# DSDLink.net
KiCad netlist of a schematic drawn in Altium Designer
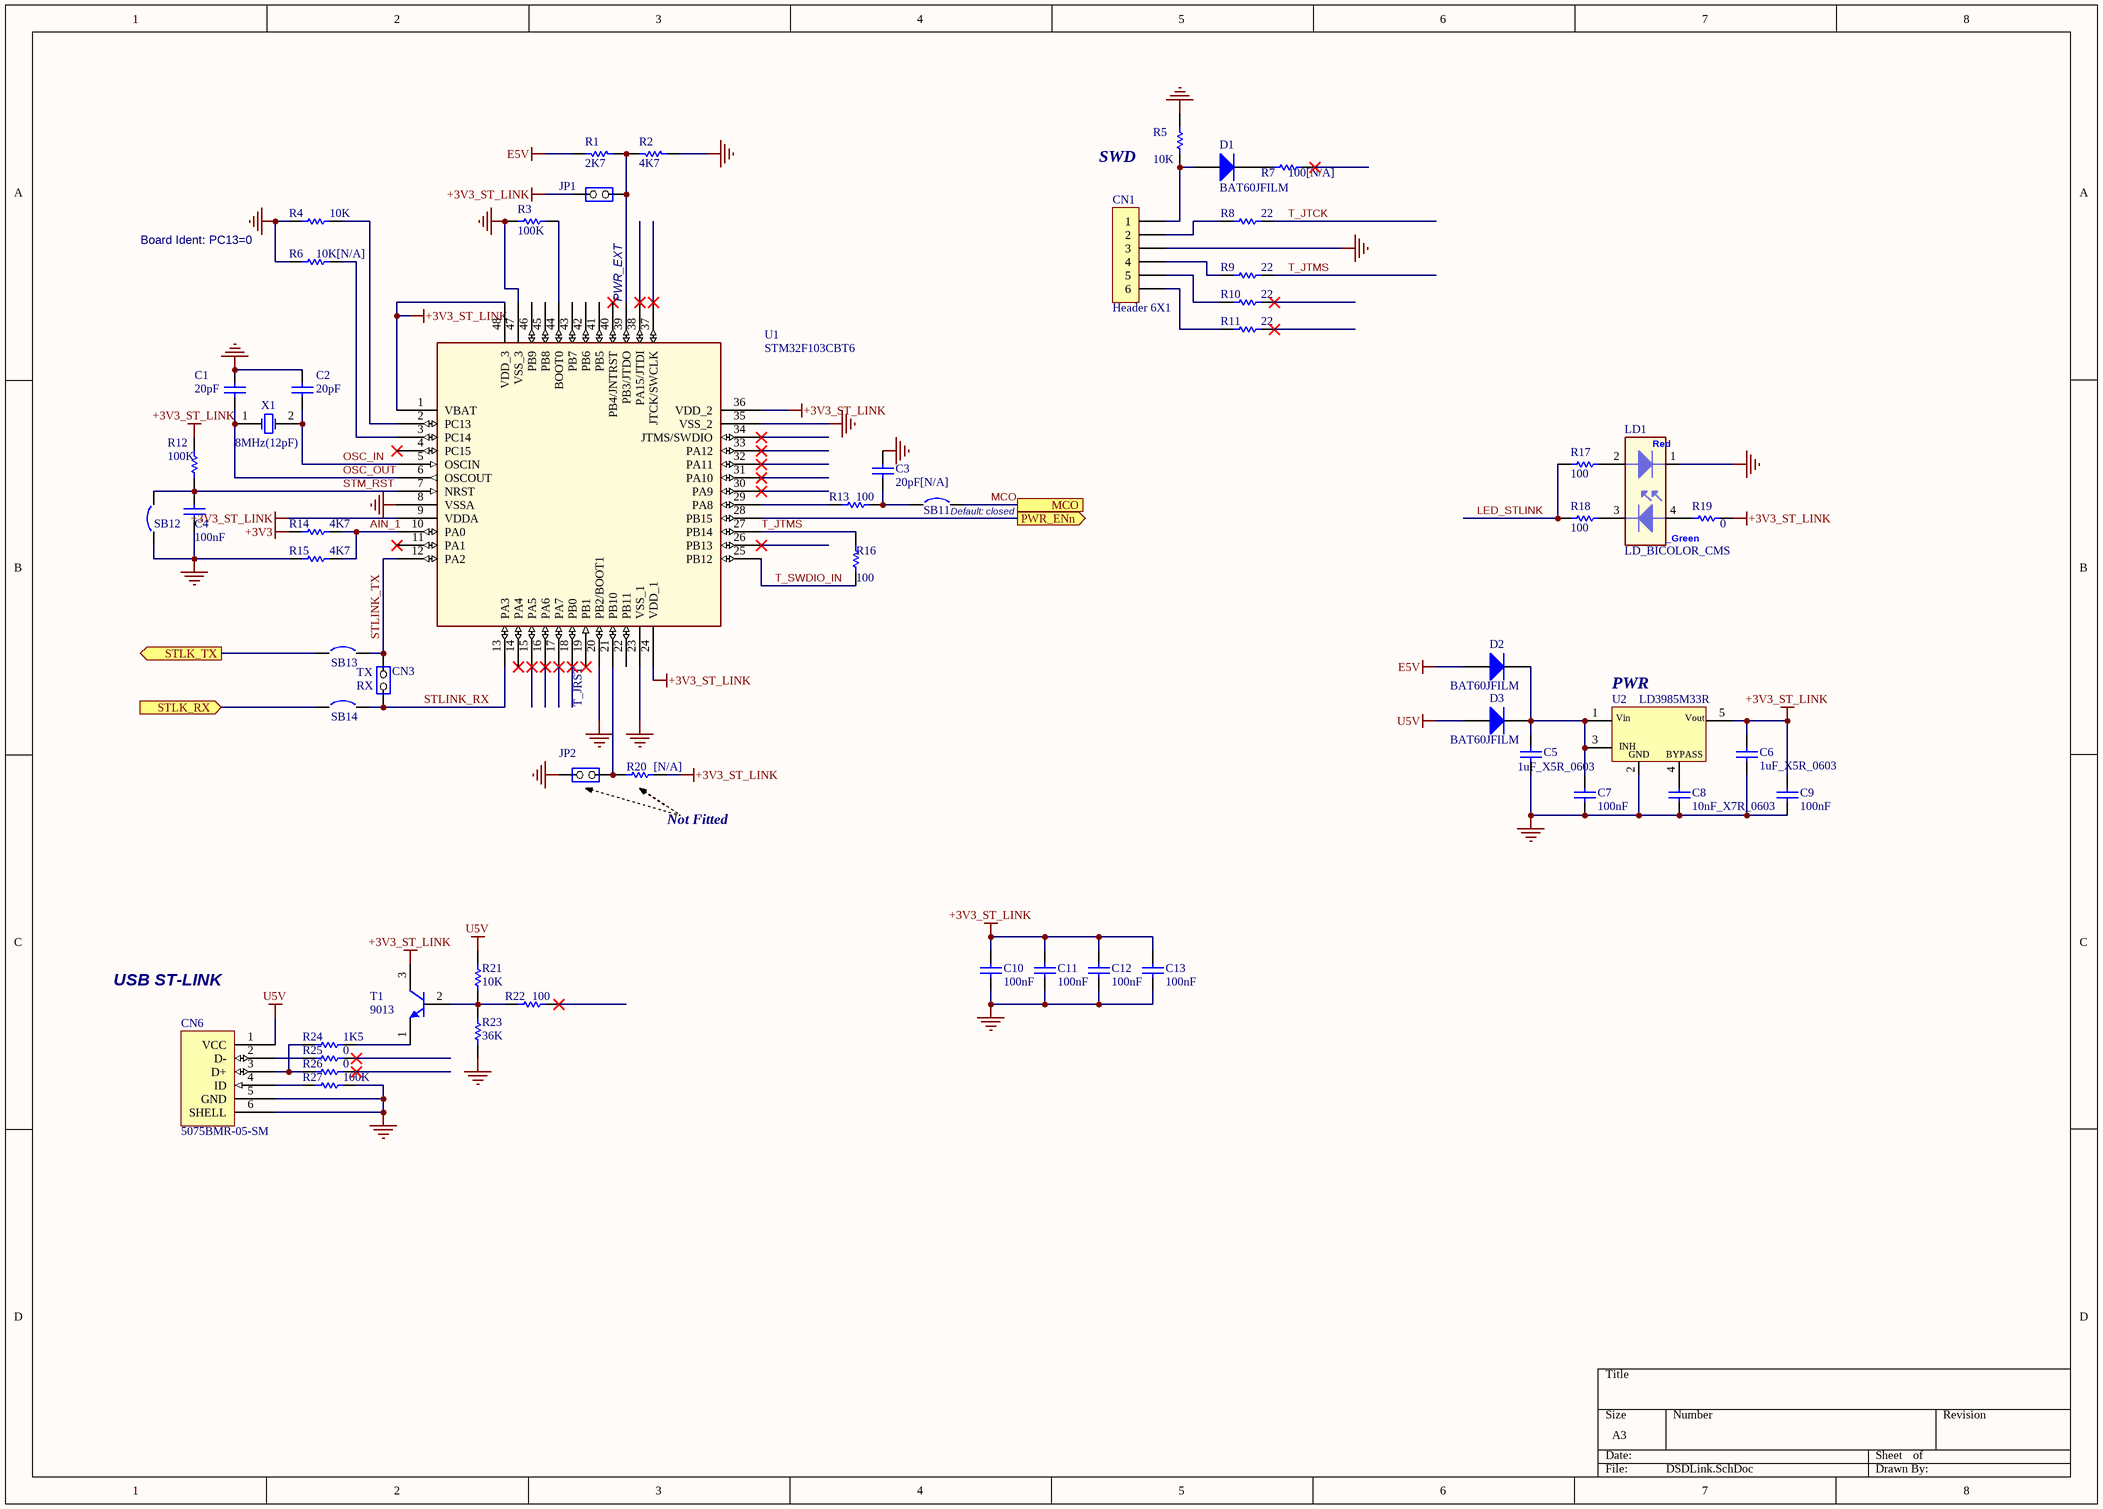
[diagram p0: DSDLink.SchDoc]

(export (version "E")
  (design (tool "Eeschema 10.0.6"))
  (components
    (comp (ref "C1")
      (value "20pF")
      (footprint "0603C")
      (description "Capacitor 0402 / 0603 / 0805")
      (libsource (lib "MCD_TOOLS") (part "Capacitor_ST"))
    )
    (comp (ref "C2")
      (value "20pF")
      (footprint "0603C")
      (description "Capacitor 0402 / 0603 / 0805")
      (libsource (lib "MCD_TOOLS") (part "Capacitor_ST"))
    )
    (comp (ref "C3")
      (value "20pF[N/A]")
      (footprint "0603C")
      (description "Capacitor 0402 / 0603 / 0805")
      (libsource (lib "MCD_TOOLS") (part "Capacitor_ST"))
    )
    (comp (ref "C4")
      (value "100nF")
      (footprint "0603C")
      (description "Capacitor 0402 / 0603 / 0805")
      (libsource (lib "MCD_TOOLS") (part "Capacitor_ST"))
    )
    (comp (ref "C5")
      (value "1uF_X5R_0603")
      (footprint "0603C")
      (description "0603  X5R 1µF")
      (fields (field (name "TOLERANCE") "10%"))
      (libsource (lib "MB963_1") (part "CAP SMD 0603  X5R 1µF 25V 10%"))
    )
    (comp (ref "C6")
      (value "1uF_X5R_0603")
      (footprint "0603C")
      (description "0603  X5R 1µF")
      (fields (field (name "TOLERANCE") "10%"))
      (libsource (lib "MB963_1") (part "CAP SMD 0603  X5R 1µF 25V 10%"))
    )
    (comp (ref "C7")
      (value "100nF")
      (footprint "0603C")
      (description "Capacitor 0402 / 0603 / 0805")
      (libsource (lib "MCD_TOOLS") (part "Capacitor_ST"))
    )
    (comp (ref "C8")
      (value "10nF_X7R_0603")
      (footprint "0603C")
      (description "0603  X7R 10NF")
      (fields (field (name "TOLERANCE") "10%"))
      (libsource (lib "MB963_1") (part "CAP SMD 0603  X7R 10000PF 50V 10%"))
    )
    (comp (ref "C9")
      (value "100nF")
      (footprint "0603C")
      (description "Capacitor 0402 / 0603 / 0805")
      (libsource (lib "MCD_TOOLS") (part "Capacitor_ST"))
    )
    (comp (ref "C10")
      (value "100nF")
      (footprint "0603C")
      (description "Capacitor 0402 / 0603 / 0805")
      (libsource (lib "MCD_TOOLS") (part "Capacitor_ST"))
    )
    (comp (ref "C11")
      (value "100nF")
      (footprint "0603C")
      (description "Capacitor 0402 / 0603 / 0805")
      (libsource (lib "MCD_TOOLS") (part "Capacitor_ST"))
    )
    (comp (ref "C12")
      (value "100nF")
      (footprint "0603C")
      (description "Capacitor 0402 / 0603 / 0805")
      (libsource (lib "MCD_TOOLS") (part "Capacitor_ST"))
    )
    (comp (ref "C13")
      (value "100nF")
      (footprint "0603C")
      (description "Capacitor 0402 / 0603 / 0805")
      (libsource (lib "MCD_TOOLS") (part "Capacitor_ST"))
    )
    (comp (ref "CN1")
      (value "Header 6X1")
      (footprint "1*6P")
      (description "Header, 6-Pin, Single row")
      (fields (field (name "PUBLISHER") "Altium Limited"))
      (libsource (lib "Nucleo_64") (part "Header 6X1"))
    )
    (comp (ref "CN3") (value "~") (footprint "SIP2/2.54") (libsource (lib "MCD_TOOLS") (part "JP2")))
    (comp (ref "CN6")
      (value "5075BMR-05-SM")
      (footprint "USB-MINI-B-SMD")
      (description "USB-MINI-typeB connector")
      (libsource (lib "MCD_TOOLS") (part "USB-MINI-typeB connector"))
    )
    (comp (ref "D1")
      (value "BAT60JFILM")
      (footprint "SOD323/A")
      (libsource (lib "MCD_TOOLS") (part "BAT60JFILM"))
    )
    (comp (ref "D2")
      (value "BAT60JFILM")
      (footprint "SOD323/A")
      (libsource (lib "MCD_TOOLS") (part "BAT60JFILM"))
    )
    (comp (ref "D3")
      (value "BAT60JFILM")
      (footprint "SOD323/A")
      (libsource (lib "MCD_TOOLS") (part "BAT60JFILM"))
    )
    (comp (ref "JP1") (value "~") (footprint "SIP2/2.54") (libsource (lib "*") (part "JP2")))
    (comp (ref "JP2") (value "~") (footprint "SIP2/2.54") (libsource (lib "*") (part "JP2")))
    (comp (ref "LD1")
      (value "LD_BICOLOR_CMS")
      (footprint "HSMF-A201")
      (description "Bicolor Led")
      (libsource (lib "MCD_TOOLS") (part "LD_BICOLOR_CMS"))
    )
    (comp (ref "R1")
      (value "2K7")
      (footprint "0603R")
      (description "Resistor")
      (fields (field (name "PUBLISHER") "Altium Limited"))
      (libsource (lib "") (part "Res1_2"))
    )
    (comp (ref "R2")
      (value "4K7")
      (footprint "0603R")
      (description "Resistor")
      (fields (field (name "PUBLISHER") "Altium Limited"))
      (libsource (lib "") (part "Res1_2"))
    )
    (comp (ref "R3")
      (value "100K")
      (footprint "0603R")
      (description "Resistor 0402 / 0603 / 0805")
      (libsource (lib "Miscellaneous Devices") (part "Res1"))
    )
    (comp (ref "R4")
      (value "10K")
      (footprint "0603R")
      (description "Resistor 0402 / 0603 / 0805")
      (libsource (lib "Miscellaneous Devices") (part "Res1"))
    )
    (comp (ref "R5")
      (value "10K")
      (footprint "0603R")
      (description "Resistor 0402 / 0603 / 0805")
      (libsource (lib "Miscellaneous Devices") (part "Res1"))
    )
    (comp (ref "R6")
      (value "10K[N/A]")
      (footprint "0603R")
      (description "Resistor 0402 / 0603 / 0805")
      (libsource (lib "Miscellaneous Devices") (part "Res1"))
    )
    (comp (ref "R7")
      (value "100[N/A]")
      (footprint "0603R")
      (description "Resistor 0402 / 0603 / 0805")
      (libsource (lib "Miscellaneous Devices") (part "Res1"))
    )
    (comp (ref "R8")
      (value "22")
      (footprint "0603R")
      (description "Resistor 0402 / 0603 / 0805")
      (libsource (lib "Miscellaneous Devices") (part "Res1"))
    )
    (comp (ref "R9")
      (value "22")
      (footprint "0603R")
      (description "Resistor 0402 / 0603 / 0805")
      (libsource (lib "Miscellaneous Devices") (part "Res1"))
    )
    (comp (ref "R10")
      (value "22")
      (footprint "0603R")
      (description "Resistor 0402 / 0603 / 0805")
      (libsource (lib "Miscellaneous Devices") (part "Res1"))
    )
    (comp (ref "R11")
      (value "22")
      (footprint "0603R")
      (description "Resistor 0402 / 0603 / 0805")
      (libsource (lib "Miscellaneous Devices") (part "Res1"))
    )
    (comp (ref "R12")
      (value "100K")
      (footprint "0603R")
      (description "Resistor 0402 / 0603 / 0805")
      (libsource (lib "Miscellaneous Devices") (part "Res1"))
    )
    (comp (ref "R13")
      (value "100")
      (footprint "0603R")
      (description "Resistor 0402 / 0603 / 0805")
      (libsource (lib "Miscellaneous Devices") (part "Res1"))
    )
    (comp (ref "R14")
      (value "4K7")
      (footprint "0603R")
      (description "Resistor 0402 / 0603 / 0805")
      (libsource (lib "Miscellaneous Devices") (part "Res1"))
    )
    (comp (ref "R15")
      (value "4K7")
      (footprint "0603R")
      (description "Resistor 0402 / 0603 / 0805")
      (libsource (lib "Miscellaneous Devices") (part "Res1"))
    )
    (comp (ref "R16")
      (value "100")
      (footprint "0603R")
      (description "Resistor 0402 / 0603 / 0805")
      (libsource (lib "Miscellaneous Devices") (part "Res1"))
    )
    (comp (ref "R17")
      (value "100")
      (footprint "0603R")
      (description "Resistor 0402 / 0603 / 0805")
      (libsource (lib "Miscellaneous Devices") (part "Res1"))
    )
    (comp (ref "R18")
      (value "100")
      (footprint "0603R")
      (description "Resistor 0402 / 0603 / 0805")
      (libsource (lib "Miscellaneous Devices") (part "Res1"))
    )
    (comp (ref "R19")
      (value "0")
      (footprint "0603R")
      (description "Resistor 0402 / 0603 / 0805")
      (libsource (lib "Miscellaneous Devices") (part "Res1"))
    )
    (comp (ref "R20")
      (value "[N/A]")
      (footprint "0603R")
      (description "Resistor")
      (fields (field (name "PUBLISHER") "Altium Limited"))
      (libsource (lib "") (part "Res1_1"))
    )
    (comp (ref "R21")
      (value "10K")
      (footprint "0603R")
      (description "Resistor")
      (fields (field (name "PUBLISHER") "Altium Limited"))
      (libsource (lib "") (part "Res1_1"))
    )
    (comp (ref "R22")
      (value "100")
      (footprint "0603R")
      (description "Resistor 0402 / 0603 / 0805")
      (libsource (lib "Miscellaneous Devices") (part "Res1"))
    )
    (comp (ref "R23")
      (value "36K")
      (footprint "0603R")
      (description "Resistor")
      (fields (field (name "PUBLISHER") "Altium Limited"))
      (libsource (lib "") (part "Res1_1"))
    )
    (comp (ref "R24")
      (value "1K5")
      (footprint "0603R")
      (description "Resistor 0402 / 0603 / 0805")
      (libsource (lib "Miscellaneous Devices") (part "Res1"))
    )
    (comp (ref "R25")
      (value "0")
      (footprint "0603R")
      (description "Resistor 0402 / 0603 / 0805")
      (libsource (lib "Miscellaneous Devices") (part "Res1"))
    )
    (comp (ref "R26")
      (value "0")
      (footprint "0603R")
      (description "Resistor 0402 / 0603 / 0805")
      (libsource (lib "Miscellaneous Devices") (part "Res1"))
    )
    (comp (ref "R27")
      (value "100K")
      (footprint "0603R")
      (description "Resistor 0402 / 0603 / 0805")
      (libsource (lib "Miscellaneous Devices") (part "Res1"))
    )
    (comp (ref "SB11")
      (value "Circuit Breaker")
      (footprint "JP2_SMD")
      (fields (field (name "PUBLISHER") "Altium Limited"))
      (libsource (lib "MCD_TOOLS") (part "Circuit Breaker"))
    )
    (comp (ref "SB12")
      (value "Circuit Breaker")
      (footprint "JP2_SMD")
      (fields (field (name "PUBLISHER") "Altium Limited"))
      (libsource (lib "MB915") (part "Circuit Breaker"))
    )
    (comp (ref "SB13")
      (value "Circuit Breaker")
      (footprint "JP2_SMD")
      (fields (field (name "PUBLISHER") "Altium Limited"))
      (libsource (lib "MCD_TOOLS") (part "Circuit Breaker"))
    )
    (comp (ref "SB14")
      (value "Circuit Breaker")
      (footprint "JP2_SMD")
      (fields (field (name "PUBLISHER") "Altium Limited"))
      (libsource (lib "MCD_TOOLS") (part "Circuit Breaker"))
    )
    (comp (ref "T1")
      (value "9013")
      (footprint "SOT-23")
      (description "NPN Bipolar Transistor")
      (fields (field (name "PUBLISHER") "Altium Limited"))
      (libsource (lib "Miscellaneous Devices") (part "NPN"))
    )
    (comp (ref "U1")
      (value "STM32F103CBT6")
      (footprint "QFP48 7X7")
      (description "Medium-density performance line ARM-based 32-bit MCU with 64KB Flash")
      (libsource (lib "Nucleo_64") (part "STM32F103CBT6"))
    )
    (comp (ref "U2")
      (value "LD3985M33R")
      (footprint "SOT-23-5L")
      (description "Ultra low drop-low noise BiCMOS voltage, regulators low ESR capacitors compatible")
      (libsource (lib "MCD_TOOLS") (part "LD3985M33R"))
    )
    (comp (ref "X1")
      (value "8MHz(12pF)")
      (footprint "XTAL1")
      (description "Crystal Oscillator")
      (fields (field (name "PUBLISHER") "Altium Limited"))
      (libsource (lib "MB963_1") (part "XTAL"))
    )
  )
  (nets
    (net (code "1") (name "+3V3") (class "Default")
      (node (ref "R14") (pin "1") (pinfunction "1_1") (pintype "passive"))
    )
    (net (code "2") (name "+3V3_ST_LINK") (class "Default")
      (node (ref "C10") (pin "2") (pinfunction "2_2") (pintype "passive"))
      (node (ref "C11") (pin "2") (pinfunction "2_2") (pintype "passive"))
      (node (ref "C12") (pin "2") (pinfunction "2_2") (pintype "passive"))
      (node (ref "C13") (pin "2") (pinfunction "2_2") (pintype "passive"))
      (node (ref "C6") (pin "1") (pinfunction "1_1") (pintype "passive"))
      (node (ref "C9") (pin "2") (pinfunction "2_2") (pintype "passive"))
      (node (ref "JP1") (pin "1") (pinfunction "COMMON_1") (pintype "passive"))
      (node (ref "R12") (pin "2") (pinfunction "2_2") (pintype "passive"))
      (node (ref "R19") (pin "2") (pinfunction "2_2") (pintype "passive"))
      (node (ref "R20") (pin "1") (pinfunction "1_1") (pintype "passive"))
      (node (ref "T1") (pin "3") (pinfunction "C_3") (pintype "passive"))
      (node (ref "U1") (pin "1") (pinfunction "VBAT_1") (pintype "power_in"))
      (node (ref "U1") (pin "24") (pinfunction "VDD_1_24") (pintype "power_in"))
      (node (ref "U1") (pin "36") (pinfunction "VDD_2_36") (pintype "power_in"))
      (node (ref "U1") (pin "48") (pinfunction "VDD_3_48") (pintype "power_in"))
      (node (ref "U1") (pin "9") (pinfunction "VDDA_9") (pintype "power_in"))
      (node (ref "U2") (pin "5") (pinfunction "Vout_5") (pintype "passive"))
    )
    (net (code "3") (name "/AIN_1") (class "Default")
      (node (ref "R14") (pin "2") (pinfunction "2_2") (pintype "passive"))
      (node (ref "R15") (pin "2") (pinfunction "2_2") (pintype "passive"))
      (node (ref "U1") (pin "10") (pinfunction "PA0_10") (pintype "bidirectional"))
    )
    (net (code "4") (name "/LED_STLINK") (class "Default")
      (node (ref "R17") (pin "1") (pinfunction "1_1") (pintype "passive"))
      (node (ref "R18") (pin "1") (pinfunction "1_1") (pintype "passive"))
    )
    (net (code "5") (name "/MCO") (class "Default")
      (node (ref "SB11") (pin "2") (pinfunction "2_2") (pintype "passive"))
    )
    (net (code "6") (name "/OSC_IN") (class "Default")
      (node (ref "C2") (pin "1") (pinfunction "1_1") (pintype "passive"))
      (node (ref "U1") (pin "5") (pinfunction "OSCIN_5") (pintype "input"))
      (node (ref "X1") (pin "2") (pinfunction "OSC2_2") (pintype "passive"))
    )
    (net (code "7") (name "/OSC_OUT") (class "Default")
      (node (ref "C1") (pin "1") (pinfunction "1_1") (pintype "passive"))
      (node (ref "U1") (pin "6") (pinfunction "OSCOUT_6") (pintype "output"))
      (node (ref "X1") (pin "1") (pinfunction "OSC1_1") (pintype "passive"))
    )
    (net (code "8") (name "/PWR_ENn") (class "Default")
      (node (ref "U1") (pin "28") (pinfunction "PB15_28") (pintype "bidirectional"))
    )
    (net (code "9") (name "/STLINK_RX") (class "Default")
      (node (ref "CN3") (pin "1") (pinfunction "COMMON_1") (pintype "passive"))
      (node (ref "SB14") (pin "2") (pinfunction "2_2") (pintype "passive"))
      (node (ref "U1") (pin "13") (pinfunction "PA3_13") (pintype "bidirectional"))
    )
    (net (code "10") (name "/STLINK_TX") (class "Default")
      (node (ref "CN3") (pin "2") (pinfunction "NO_2") (pintype "passive"))
      (node (ref "SB13") (pin "2") (pinfunction "2_2") (pintype "passive"))
      (node (ref "U1") (pin "12") (pinfunction "PA2_12") (pintype "bidirectional"))
    )
    (net (code "11") (name "/STLK_RX") (class "Default")
      (node (ref "SB14") (pin "1") (pinfunction "1_1") (pintype "passive"))
    )
    (net (code "12") (name "/STLK_TX") (class "Default")
      (node (ref "SB13") (pin "1") (pinfunction "1_1") (pintype "passive"))
    )
    (net (code "13") (name "/STM_RST") (class "Default")
      (node (ref "C4") (pin "2") (pinfunction "2_2") (pintype "passive"))
      (node (ref "R12") (pin "1") (pinfunction "1_1") (pintype "passive"))
      (node (ref "SB12") (pin "2") (pinfunction "2_2") (pintype "passive"))
      (node (ref "U1") (pin "7") (pinfunction "NRST_7") (pintype "input"))
    )
    (net (code "14") (name "/T_JTCK") (class "Default")
      (node (ref "R8") (pin "2") (pinfunction "2_2") (pintype "passive"))
    )
    (net (code "15") (name "/T_JTMS") (class "Default")
      (node (ref "R16") (pin "2") (pinfunction "2_2") (pintype "passive"))
      (node (ref "R9") (pin "2") (pinfunction "2_2") (pintype "passive"))
      (node (ref "U1") (pin "27") (pinfunction "PB14_27") (pintype "bidirectional"))
    )
    (net (code "16") (name "/T_SWDIO_IN") (class "Default")
      (node (ref "R16") (pin "1") (pinfunction "1_1") (pintype "passive"))
      (node (ref "U1") (pin "25") (pinfunction "PB12_25") (pintype "bidirectional"))
    )
    (net (code "17") (name "E5V") (class "Default")
      (node (ref "D2") (pin "1") (pinfunction "A_1") (pintype "passive"))
      (node (ref "R1") (pin "1") (pinfunction "1_1") (pintype "passive"))
    )
    (net (code "18") (name "GND") (class "Default")
      (node (ref "C1") (pin "2") (pinfunction "2_2") (pintype "passive"))
      (node (ref "C10") (pin "1") (pinfunction "1_1") (pintype "passive"))
      (node (ref "C11") (pin "1") (pinfunction "1_1") (pintype "passive"))
      (node (ref "C12") (pin "1") (pinfunction "1_1") (pintype "passive"))
      (node (ref "C13") (pin "1") (pinfunction "1_1") (pintype "passive"))
      (node (ref "C2") (pin "2") (pinfunction "2_2") (pintype "passive"))
      (node (ref "C3") (pin "2") (pinfunction "2_2") (pintype "passive"))
      (node (ref "C4") (pin "1") (pinfunction "1_1") (pintype "passive"))
      (node (ref "C5") (pin "1") (pinfunction "1_1") (pintype "passive"))
      (node (ref "C6") (pin "2") (pinfunction "2_2") (pintype "passive"))
      (node (ref "C7") (pin "1") (pinfunction "1_1") (pintype "passive"))
      (node (ref "C8") (pin "1") (pinfunction "1_1") (pintype "passive"))
      (node (ref "C9") (pin "1") (pinfunction "1_1") (pintype "passive"))
      (node (ref "CN1") (pin "3") (pinfunction "3_3") (pintype "passive"))
      (node (ref "CN6") (pin "5") (pinfunction "GND_5") (pintype "power_in"))
      (node (ref "CN6") (pin "6") (pinfunction "SHELL_6") (pintype "power_in"))
      (node (ref "JP2") (pin "1") (pinfunction "COMMON_1") (pintype "passive"))
      (node (ref "LD1") (pin "1") (pinfunction "1_1") (pintype "passive"))
      (node (ref "R15") (pin "1") (pinfunction "1_1") (pintype "passive"))
      (node (ref "R2") (pin "2") (pinfunction "2_2") (pintype "passive"))
      (node (ref "R23") (pin "1") (pinfunction "1_1") (pintype "passive"))
      (node (ref "R27") (pin "2") (pinfunction "2_2") (pintype "passive"))
      (node (ref "R3") (pin "1") (pinfunction "1_1") (pintype "passive"))
      (node (ref "R4") (pin "1") (pinfunction "1_1") (pintype "passive"))
      (node (ref "R5") (pin "2") (pinfunction "2_2") (pintype "passive"))
      (node (ref "R6") (pin "1") (pinfunction "1_1") (pintype "passive"))
      (node (ref "SB12") (pin "1") (pinfunction "1_1") (pintype "passive"))
      (node (ref "U1") (pin "20") (pinfunction "PB2/BOOT1_20") (pintype "bidirectional"))
      (node (ref "U1") (pin "23") (pinfunction "VSS_1_23") (pintype "power_in"))
      (node (ref "U1") (pin "35") (pinfunction "VSS_2_35") (pintype "power_in"))
      (node (ref "U1") (pin "47") (pinfunction "VSS_3_47") (pintype "power_in"))
      (node (ref "U1") (pin "8") (pinfunction "VSSA_8") (pintype "power_in"))
      (node (ref "U2") (pin "2") (pinfunction "GND_2") (pintype "passive"))
    )
    (net (code "19") (name "Net-(C3-Pad1)") (class "Default")
      (node (ref "C3") (pin "1") (pinfunction "1_1") (pintype "passive"))
      (node (ref "R13") (pin "2") (pinfunction "2_2") (pintype "passive"))
      (node (ref "SB11") (pin "1") (pinfunction "1_1") (pintype "passive"))
    )
    (net (code "20") (name "Net-(CN1-Pad2)") (class "Default")
      (node (ref "CN1") (pin "2") (pinfunction "2_2") (pintype "passive"))
      (node (ref "R8") (pin "1") (pinfunction "1_1") (pintype "passive"))
    )
    (net (code "21") (name "Net-(CN1-Pad4)") (class "Default")
      (node (ref "CN1") (pin "4") (pinfunction "4_4") (pintype "passive"))
      (node (ref "R9") (pin "1") (pinfunction "1_1") (pintype "passive"))
    )
    (net (code "22") (name "Net-(CN1-Pad5)") (class "Default")
      (node (ref "CN1") (pin "5") (pinfunction "5_5") (pintype "passive"))
      (node (ref "R10") (pin "1") (pinfunction "1_1") (pintype "passive"))
    )
    (net (code "23") (name "Net-(CN1-Pad6)") (class "Default")
      (node (ref "CN1") (pin "6") (pinfunction "6_6") (pintype "passive"))
      (node (ref "R11") (pin "1") (pinfunction "1_1") (pintype "passive"))
    )
    (net (code "24") (name "Net-(CN6-D+)") (class "Default")
      (node (ref "CN6") (pin "3") (pinfunction "D+_3") (pintype "bidirectional"))
      (node (ref "R24") (pin "1") (pinfunction "1_1") (pintype "passive"))
      (node (ref "R26") (pin "1") (pinfunction "1_1") (pintype "passive"))
    )
    (net (code "25") (name "Net-(CN6-D-)") (class "Default")
      (node (ref "CN6") (pin "2") (pinfunction "D-_2") (pintype "bidirectional"))
      (node (ref "R25") (pin "1") (pinfunction "1_1") (pintype "passive"))
    )
    (net (code "26") (name "Net-(CN6-ID)") (class "Default")
      (node (ref "CN6") (pin "4") (pinfunction "ID_4") (pintype "input"))
      (node (ref "R27") (pin "1") (pinfunction "1_1") (pintype "passive"))
    )
    (net (code "27") (name "Net-(D1-A)") (class "Default")
      (node (ref "CN1") (pin "1") (pinfunction "1_1") (pintype "passive"))
      (node (ref "D1") (pin "1") (pinfunction "A_1") (pintype "passive"))
      (node (ref "R5") (pin "1") (pinfunction "1_1") (pintype "passive"))
    )
    (net (code "28") (name "Net-(D1-K)") (class "Default")
      (node (ref "D1") (pin "2") (pinfunction "K_2") (pintype "passive"))
      (node (ref "R7") (pin "1") (pinfunction "1_1") (pintype "passive"))
    )
    (net (code "29") (name "Net-(D2-K)") (class "Default")
      (node (ref "C5") (pin "2") (pinfunction "2_2") (pintype "passive"))
      (node (ref "C7") (pin "2") (pinfunction "2_2") (pintype "passive"))
      (node (ref "D2") (pin "2") (pinfunction "K_2") (pintype "passive"))
      (node (ref "D3") (pin "2") (pinfunction "K_2") (pintype "passive"))
      (node (ref "U2") (pin "1") (pinfunction "Vin_1") (pintype "passive"))
      (node (ref "U2") (pin "3") (pinfunction "CE_3") (pintype "passive"))
    )
    (net (code "30") (name "Net-(JP1-NO)") (class "Default")
      (node (ref "JP1") (pin "2") (pinfunction "NO_2") (pintype "passive"))
      (node (ref "R1") (pin "2") (pinfunction "2_2") (pintype "passive"))
      (node (ref "R2") (pin "1") (pinfunction "1_1") (pintype "passive"))
      (node (ref "U1") (pin "39") (pinfunction "PB3/JTDO_39") (pintype "bidirectional"))
    )
    (net (code "31") (name "Net-(JP2-NO)") (class "Default")
      (node (ref "JP2") (pin "2") (pinfunction "NO_2") (pintype "passive"))
      (node (ref "R20") (pin "2") (pinfunction "2_2") (pintype "passive"))
      (node (ref "U1") (pin "21") (pinfunction "PB10_21") (pintype "bidirectional"))
    )
    (net (code "32") (name "Net-(LD1-Pad2)") (class "Default")
      (node (ref "LD1") (pin "2") (pinfunction "2_2") (pintype "passive"))
      (node (ref "R17") (pin "2") (pinfunction "2_2") (pintype "passive"))
    )
    (net (code "33") (name "Net-(LD1-Pad3)") (class "Default")
      (node (ref "LD1") (pin "3") (pinfunction "3_3") (pintype "passive"))
      (node (ref "R18") (pin "2") (pinfunction "2_2") (pintype "passive"))
    )
    (net (code "34") (name "Net-(LD1-Pad4)") (class "Default")
      (node (ref "LD1") (pin "4") (pinfunction "4_4") (pintype "passive"))
      (node (ref "R19") (pin "1") (pinfunction "1_1") (pintype "passive"))
    )
    (net (code "35") (name "Net-(T1-B)") (class "Default")
      (node (ref "R21") (pin "1") (pinfunction "1_1") (pintype "passive"))
      (node (ref "R22") (pin "1") (pinfunction "1_1") (pintype "passive"))
      (node (ref "R23") (pin "2") (pinfunction "2_2") (pintype "passive"))
      (node (ref "T1") (pin "2") (pinfunction "B_2") (pintype "passive"))
    )
    (net (code "36") (name "Net-(T1-E)") (class "Default")
      (node (ref "R24") (pin "2") (pinfunction "2_2") (pintype "passive"))
      (node (ref "T1") (pin "1") (pinfunction "E_1") (pintype "passive"))
    )
    (net (code "37") (name "Net-(U1-BOOT0)") (class "Default")
      (node (ref "R3") (pin "2") (pinfunction "2_2") (pintype "passive"))
      (node (ref "U1") (pin "44") (pinfunction "BOOT0_44") (pintype "bidirectional"))
    )
    (net (code "38") (name "Net-(U1-PA8)") (class "Default")
      (node (ref "R13") (pin "1") (pinfunction "1_1") (pintype "passive"))
      (node (ref "U1") (pin "29") (pinfunction "PA8_29") (pintype "bidirectional"))
    )
    (net (code "39") (name "Net-(U1-PC13)") (class "Default")
      (node (ref "R4") (pin "2") (pinfunction "2_2") (pintype "passive"))
      (node (ref "U1") (pin "2") (pinfunction "PC13_2") (pintype "bidirectional"))
    )
    (net (code "40") (name "Net-(U1-PC14)") (class "Default")
      (node (ref "R6") (pin "2") (pinfunction "2_2") (pintype "passive"))
      (node (ref "U1") (pin "3") (pinfunction "PC14_3") (pintype "bidirectional"))
    )
    (net (code "41") (name "Net-(U2-BYPASS)") (class "Default")
      (node (ref "C8") (pin "2") (pinfunction "2_2") (pintype "passive"))
      (node (ref "U2") (pin "4") (pinfunction "BYPASS_4") (pintype "passive"))
    )
    (net (code "42") (name "U5V") (class "Default")
      (node (ref "CN6") (pin "1") (pinfunction "VCC_1") (pintype "power_in"))
      (node (ref "D3") (pin "1") (pinfunction "A_1") (pintype "passive"))
      (node (ref "R21") (pin "2") (pinfunction "2_2") (pintype "passive"))
    )
    (net (code "43") (name "unconnected-(R7-Pad2)") (class "Default")
      (node (ref "R7") (pin "2") (pinfunction "2_2") (pintype "passive+no_connect"))
    )
    (net (code "44") (name "unconnected-(R10-Pad2)") (class "Default")
      (node (ref "R10") (pin "2") (pinfunction "2_2") (pintype "passive+no_connect"))
    )
    (net (code "45") (name "unconnected-(R11-Pad2)") (class "Default")
      (node (ref "R11") (pin "2") (pinfunction "2_2") (pintype "passive+no_connect"))
    )
    (net (code "46") (name "unconnected-(R22-Pad2)") (class "Default")
      (node (ref "R22") (pin "2") (pinfunction "2_2") (pintype "passive+no_connect"))
    )
    (net (code "47") (name "unconnected-(R25-Pad2)") (class "Default")
      (node (ref "R25") (pin "2") (pinfunction "2_2") (pintype "passive+no_connect"))
    )
    (net (code "48") (name "unconnected-(R26-Pad2)") (class "Default")
      (node (ref "R26") (pin "2") (pinfunction "2_2") (pintype "passive+no_connect"))
    )
    (net (code "49") (name "unconnected-(U1-JTCK{slash}SWCLK-Pad37)") (class "Default")
      (node (ref "U1") (pin "37") (pinfunction "JTCK/SWCLK_37") (pintype "bidirectional+no_connect"))
    )
    (net (code "50") (name "unconnected-(U1-JTMS{slash}SWDIO-Pad34)") (class "Default")
      (node (ref "U1") (pin "34") (pinfunction "JTMS/SWDIO_34") (pintype "bidirectional+no_connect"))
    )
    (net (code "51") (name "unconnected-(U1-PA1-Pad11)") (class "Default")
      (node (ref "U1") (pin "11") (pinfunction "PA1_11") (pintype "bidirectional+no_connect"))
    )
    (net (code "52") (name "unconnected-(U1-PA4-Pad14)") (class "Default")
      (node (ref "U1") (pin "14") (pinfunction "PA4_14") (pintype "bidirectional+no_connect"))
    )
    (net (code "53") (name "unconnected-(U1-PA5-Pad15)") (class "Default")
      (node (ref "U1") (pin "15") (pinfunction "PA5_15") (pintype "bidirectional+no_connect"))
    )
    (net (code "54") (name "unconnected-(U1-PA6-Pad16)") (class "Default")
      (node (ref "U1") (pin "16") (pinfunction "PA6_16") (pintype "bidirectional+no_connect"))
    )
    (net (code "55") (name "unconnected-(U1-PA7-Pad17)") (class "Default")
      (node (ref "U1") (pin "17") (pinfunction "PA7_17") (pintype "bidirectional+no_connect"))
    )
    (net (code "56") (name "unconnected-(U1-PA9-Pad30)") (class "Default")
      (node (ref "U1") (pin "30") (pinfunction "PA9_30") (pintype "bidirectional+no_connect"))
    )
    (net (code "57") (name "unconnected-(U1-PA10-Pad31)") (class "Default")
      (node (ref "U1") (pin "31") (pinfunction "PA10_31") (pintype "bidirectional+no_connect"))
    )
    (net (code "58") (name "unconnected-(U1-PA11-Pad32)") (class "Default")
      (node (ref "U1") (pin "32") (pinfunction "PA11_32") (pintype "bidirectional+no_connect"))
    )
    (net (code "59") (name "unconnected-(U1-PA12-Pad33)") (class "Default")
      (node (ref "U1") (pin "33") (pinfunction "PA12_33") (pintype "bidirectional+no_connect"))
    )
    (net (code "60") (name "unconnected-(U1-PA15{slash}JTDI-Pad38)") (class "Default")
      (node (ref "U1") (pin "38") (pinfunction "PA15/JTDI_38") (pintype "bidirectional+no_connect"))
    )
    (net (code "61") (name "unconnected-(U1-PB0-Pad18)") (class "Default")
      (node (ref "U1") (pin "18") (pinfunction "PB0_18") (pintype "bidirectional+no_connect"))
    )
    (net (code "62") (name "unconnected-(U1-PB1-Pad19)") (class "Default")
      (node (ref "U1") (pin "19") (pinfunction "PB1_19") (pintype "input+no_connect"))
    )
    (net (code "63") (name "unconnected-(U1-PB4{slash}JNTRST-Pad40)") (class "Default")
      (node (ref "U1") (pin "40") (pinfunction "PB4/JNTRST_40") (pintype "bidirectional+no_connect"))
    )
    (net (code "64") (name "unconnected-(U1-PB5-Pad41)") (class "Default")
      (node (ref "U1") (pin "41") (pinfunction "PB5_41") (pintype "bidirectional"))
    )
    (net (code "65") (name "unconnected-(U1-PB6-Pad42)") (class "Default")
      (node (ref "U1") (pin "42") (pinfunction "PB6_42") (pintype "bidirectional"))
    )
    (net (code "66") (name "unconnected-(U1-PB7-Pad43)") (class "Default")
      (node (ref "U1") (pin "43") (pinfunction "PB7_43") (pintype "bidirectional"))
    )
    (net (code "67") (name "unconnected-(U1-PB8-Pad45)") (class "Default")
      (node (ref "U1") (pin "45") (pinfunction "PB8_45") (pintype "bidirectional"))
    )
    (net (code "68") (name "unconnected-(U1-PB9-Pad46)") (class "Default")
      (node (ref "U1") (pin "46") (pinfunction "PB9_46") (pintype "bidirectional"))
    )
    (net (code "69") (name "unconnected-(U1-PB11-Pad22)") (class "Default")
      (node (ref "U1") (pin "22") (pinfunction "PB11_22") (pintype "bidirectional"))
    )
    (net (code "70") (name "unconnected-(U1-PB13-Pad26)") (class "Default")
      (node (ref "U1") (pin "26") (pinfunction "PB13_26") (pintype "bidirectional+no_connect"))
    )
    (net (code "71") (name "unconnected-(U1-PC15-Pad4)") (class "Default")
      (node (ref "U1") (pin "4") (pinfunction "PC15_4") (pintype "bidirectional+no_connect"))
    )
  )
)
